# Lock.net
KiCad netlist of a schematic drawn in EAGLE
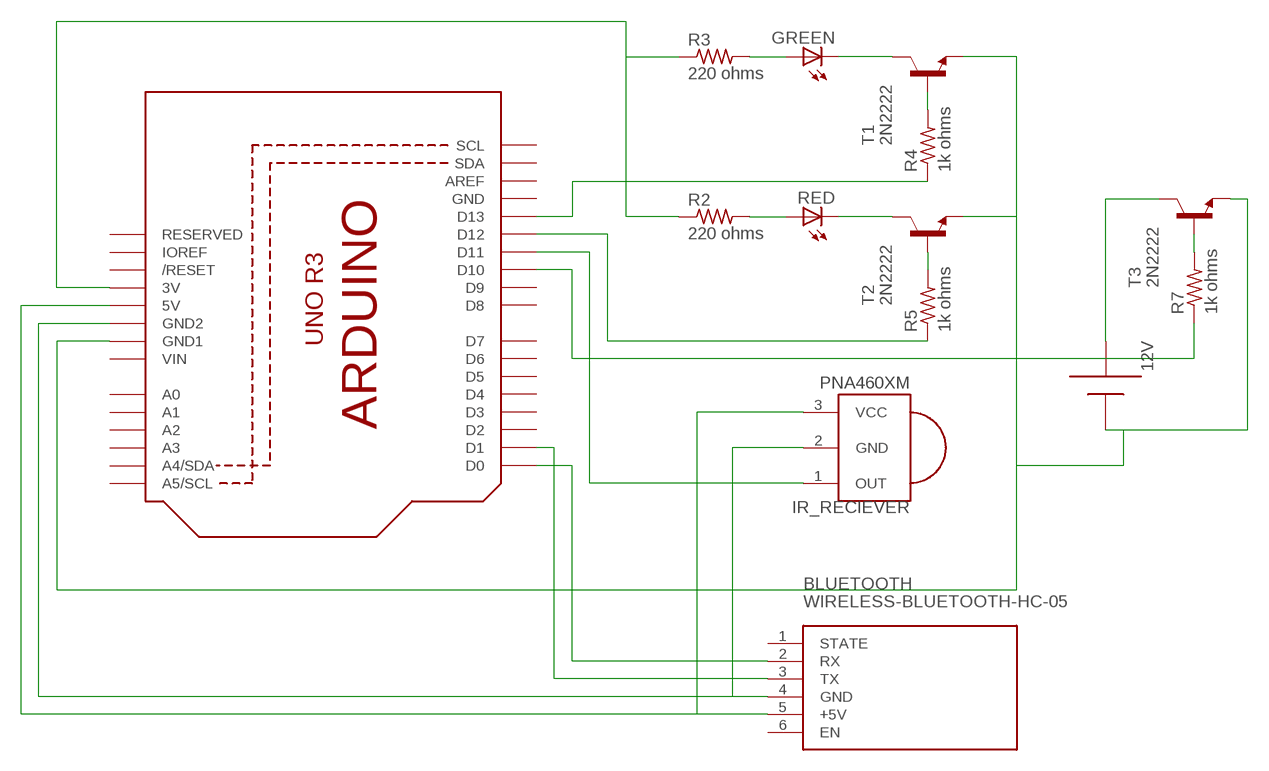
[diagram p0: schematic, sheet 1]

(export (version "E")
  (design (tool "Eeschema 10.0.6"))
  (components
    (comp (ref "12V")
      (value "AAA")
      (footprint "eagle-import:12BH412")
      (libsource (lib "eagle-import") (part "AAA"))
    )
    (comp (ref "BLUETOOTH")
      (value "WIRELESS-BLUETOOTH-HC-05")
      (footprint "eagle-import:WIRELESS-BLUETOOTH-HC-05")
      (libsource (lib "eagle-import") (part "WIRELESS-BLUETOOTH-HC-05"))
    )
    (comp (ref "GREEN")
      (value "LED3MM")
      (footprint "eagle-import:LED3MM")
      (libsource (lib "eagle-import") (part "LED3MM"))
    )
    (comp (ref "IR_RECIEVER")
      (value "PNA460XM")
      (footprint "eagle-import:PNA460XM")
      (libsource (lib "eagle-import") (part "PNA460XM"))
    )
    (comp (ref "R2")
      (value "220 ohms")
      (footprint "eagle-import:R1005")
      (libsource (lib "eagle-import") (part "R-US_R1005"))
    )
    (comp (ref "R3")
      (value "220 ohms")
      (footprint "eagle-import:R1005")
      (libsource (lib "eagle-import") (part "R-US_R1005"))
    )
    (comp (ref "R4")
      (value "1k ohms")
      (footprint "eagle-import:R1005")
      (libsource (lib "eagle-import") (part "R-US_R1005"))
    )
    (comp (ref "R5")
      (value "1k ohms")
      (footprint "eagle-import:R1005")
      (libsource (lib "eagle-import") (part "R-US_R1005"))
    )
    (comp (ref "R7")
      (value "1k ohms")
      (footprint "eagle-import:R1005")
      (libsource (lib "eagle-import") (part "R-US_R1005"))
    )
    (comp (ref "RED")
      (value "LED3MM")
      (footprint "eagle-import:LED3MM")
      (libsource (lib "eagle-import") (part "LED3MM"))
    )
    (comp (ref "T1")
      (value "2N2222")
      (footprint "eagle-import:TO92-EBC-OVAL")
      (libsource (lib "eagle-import") (part "2N2222"))
    )
    (comp (ref "T2")
      (value "2N2222")
      (footprint "eagle-import:TO92-EBC-OVAL")
      (libsource (lib "eagle-import") (part "2N2222"))
    )
    (comp (ref "T3")
      (value "2N2222")
      (footprint "eagle-import:TO92-EBC-OVAL")
      (libsource (lib "eagle-import") (part "2N2222"))
    )
    (comp (ref "U1")
      (value "ARDUINOR3-BPLACE")
      (footprint "eagle-import:ARDUINOR3-BPLACE")
      (libsource (lib "eagle-import") (part "ARDUINOR3-BPLACE"))
    )
  )
  (nets
    (net (code "1") (name "/GND") (class "Default")
      (node (ref "U1") (pin "GND") (pinfunction "GND_GND") (pintype "power_in"))
    )
    (net (code "2") (name "/VIN") (class "Default")
      (node (ref "U1") (pin "VIN") (pinfunction "VIN_VIN") (pintype "power_in"))
    )
    (net (code "3") (name "Net-(12V-Pad+)") (class "Default")
      (node (ref "12V") (pin "+") (pinfunction "+_+") (pintype "bidirectional"))
      (node (ref "T1") (pin "E") (pinfunction "E_E") (pintype "passive"))
      (node (ref "T2") (pin "E") (pinfunction "E_E") (pintype "passive"))
      (node (ref "T3") (pin "E") (pinfunction "E_E") (pintype "passive"))
      (node (ref "U1") (pin "GND1") (pinfunction "GND1_GND1") (pintype "power_in"))
    )
    (net (code "4") (name "Net-(12V-Pad-)") (class "Default")
      (node (ref "12V") (pin "-") (pinfunction "-_-") (pintype "bidirectional"))
      (node (ref "T3") (pin "C") (pinfunction "C_C") (pintype "passive"))
    )
    (net (code "5") (name "Net-(BLUETOOTH-+5V)") (class "Default")
      (node (ref "BLUETOOTH") (pin "5") (pinfunction "+5V_5") (pintype "power_in"))
      (node (ref "IR_RECIEVER") (pin "3") (pinfunction "VCC_3") (pintype "power_in"))
      (node (ref "U1") (pin "5V") (pinfunction "5V_5V") (pintype "power_in"))
    )
    (net (code "6") (name "Net-(BLUETOOTH-GND)") (class "Default")
      (node (ref "BLUETOOTH") (pin "4") (pinfunction "GND_4") (pintype "power_in"))
      (node (ref "IR_RECIEVER") (pin "2") (pinfunction "GND_2") (pintype "power_in"))
      (node (ref "U1") (pin "GND2") (pinfunction "GND2_GND2") (pintype "power_in"))
    )
    (net (code "7") (name "Net-(BLUETOOTH-RX)") (class "Default")
      (node (ref "BLUETOOTH") (pin "2") (pinfunction "RX_2") (pintype "bidirectional"))
      (node (ref "U1") (pin "D0") (pinfunction "D0_D0") (pintype "bidirectional"))
    )
    (net (code "8") (name "Net-(BLUETOOTH-TX)") (class "Default")
      (node (ref "BLUETOOTH") (pin "3") (pinfunction "TX_3") (pintype "bidirectional"))
      (node (ref "U1") (pin "D1") (pinfunction "D1_D1") (pintype "bidirectional"))
    )
    (net (code "9") (name "Net-(GREEN-C)") (class "Default")
      (node (ref "GREEN") (pin "K") (pinfunction "C_K") (pintype "passive"))
      (node (ref "T1") (pin "C") (pinfunction "C_C") (pintype "passive"))
    )
    (net (code "10") (name "Net-(GREEN-PadA)") (class "Default")
      (node (ref "GREEN") (pin "A") (pinfunction "A_A") (pintype "passive"))
      (node (ref "R3") (pin "2") (pinfunction "2_2") (pintype "passive"))
    )
    (net (code "11") (name "Net-(IR_RECIEVER-OUT)") (class "Default")
      (node (ref "IR_RECIEVER") (pin "1") (pinfunction "OUT_1") (pintype "output"))
      (node (ref "U1") (pin "D11") (pinfunction "D11_D11") (pintype "bidirectional"))
    )
    (net (code "12") (name "Net-(R2-Pad1)") (class "Default")
      (node (ref "R2") (pin "1") (pinfunction "1_1") (pintype "passive"))
      (node (ref "R3") (pin "1") (pinfunction "1_1") (pintype "passive"))
      (node (ref "U1") (pin "3V") (pinfunction "3V_3V") (pintype "power_in"))
    )
    (net (code "13") (name "Net-(R2-Pad2)") (class "Default")
      (node (ref "R2") (pin "2") (pinfunction "2_2") (pintype "passive"))
      (node (ref "RED") (pin "A") (pinfunction "A_A") (pintype "passive"))
    )
    (net (code "14") (name "Net-(R4-Pad1)") (class "Default")
      (node (ref "R4") (pin "1") (pinfunction "1_1") (pintype "passive"))
      (node (ref "U1") (pin "D13") (pinfunction "D13_D13") (pintype "bidirectional"))
    )
    (net (code "15") (name "Net-(R4-Pad2)") (class "Default")
      (node (ref "R4") (pin "2") (pinfunction "2_2") (pintype "passive"))
      (node (ref "T1") (pin "B") (pinfunction "B_B") (pintype "passive"))
    )
    (net (code "16") (name "Net-(R5-Pad1)") (class "Default")
      (node (ref "R5") (pin "1") (pinfunction "1_1") (pintype "passive"))
      (node (ref "U1") (pin "D12") (pinfunction "D12_D12") (pintype "bidirectional"))
    )
    (net (code "17") (name "Net-(R5-Pad2)") (class "Default")
      (node (ref "R5") (pin "2") (pinfunction "2_2") (pintype "passive"))
      (node (ref "T2") (pin "B") (pinfunction "B_B") (pintype "passive"))
    )
    (net (code "18") (name "Net-(R7-Pad1)") (class "Default")
      (node (ref "R7") (pin "1") (pinfunction "1_1") (pintype "passive"))
      (node (ref "U1") (pin "D10") (pinfunction "D10_D10") (pintype "bidirectional"))
    )
    (net (code "19") (name "Net-(R7-Pad2)") (class "Default")
      (node (ref "R7") (pin "2") (pinfunction "2_2") (pintype "passive"))
      (node (ref "T3") (pin "B") (pinfunction "B_B") (pintype "passive"))
    )
    (net (code "20") (name "Net-(RED-C)") (class "Default")
      (node (ref "RED") (pin "K") (pinfunction "C_K") (pintype "passive"))
      (node (ref "T2") (pin "C") (pinfunction "C_C") (pintype "passive"))
    )
    (net (code "21") (name "unconnected-(BLUETOOTH-EN-Pad6)") (class "Default")
      (node (ref "BLUETOOTH") (pin "6") (pinfunction "EN_6") (pintype "bidirectional"))
    )
    (net (code "22") (name "unconnected-(BLUETOOTH-STATE-Pad1)") (class "Default")
      (node (ref "BLUETOOTH") (pin "1") (pinfunction "STATE_1") (pintype "bidirectional"))
    )
    (net (code "23") (name "unconnected-(U1-A4{slash}SDA-PadA4)") (class "Default")
      (node (ref "U1") (pin "A4") (pinfunction "A4/SDA_A4") (pintype "bidirectional"))
    )
    (net (code "24") (name "unconnected-(U1-A5{slash}SCL-PadA5)") (class "Default")
      (node (ref "U1") (pin "A5") (pinfunction "A5/SCL_A5") (pintype "bidirectional"))
    )
    (net (code "25") (name "unconnected-(U1-PadA0)") (class "Default")
      (node (ref "U1") (pin "A0") (pinfunction "A0_A0") (pintype "bidirectional"))
    )
    (net (code "26") (name "unconnected-(U1-PadA1)") (class "Default")
      (node (ref "U1") (pin "A1") (pinfunction "A1_A1") (pintype "bidirectional"))
    )
    (net (code "27") (name "unconnected-(U1-PadA2)") (class "Default")
      (node (ref "U1") (pin "A2") (pinfunction "A2_A2") (pintype "bidirectional"))
    )
    (net (code "28") (name "unconnected-(U1-PadA3)") (class "Default")
      (node (ref "U1") (pin "A3") (pinfunction "A3_A3") (pintype "bidirectional"))
    )
    (net (code "29") (name "unconnected-(U1-PadAREF)") (class "Default")
      (node (ref "U1") (pin "AREF") (pinfunction "AREF_AREF") (pintype "bidirectional"))
    )
    (net (code "30") (name "unconnected-(U1-PadD2)") (class "Default")
      (node (ref "U1") (pin "D2") (pinfunction "D2_D2") (pintype "bidirectional"))
    )
    (net (code "31") (name "unconnected-(U1-PadD3)") (class "Default")
      (node (ref "U1") (pin "D3") (pinfunction "D3_D3") (pintype "bidirectional"))
    )
    (net (code "32") (name "unconnected-(U1-PadD4)") (class "Default")
      (node (ref "U1") (pin "D4") (pinfunction "D4_D4") (pintype "bidirectional"))
    )
    (net (code "33") (name "unconnected-(U1-PadD5)") (class "Default")
      (node (ref "U1") (pin "D5") (pinfunction "D5_D5") (pintype "bidirectional"))
    )
    (net (code "34") (name "unconnected-(U1-PadD6)") (class "Default")
      (node (ref "U1") (pin "D6") (pinfunction "D6_D6") (pintype "bidirectional"))
    )
    (net (code "35") (name "unconnected-(U1-PadD7)") (class "Default")
      (node (ref "U1") (pin "D7") (pinfunction "D7_D7") (pintype "bidirectional"))
    )
    (net (code "36") (name "unconnected-(U1-PadD8)") (class "Default")
      (node (ref "U1") (pin "D8") (pinfunction "D8_D8") (pintype "bidirectional"))
    )
    (net (code "37") (name "unconnected-(U1-PadD9)") (class "Default")
      (node (ref "U1") (pin "D9") (pinfunction "D9_D9") (pintype "bidirectional"))
    )
    (net (code "38") (name "unconnected-(U1-PadIOREF)") (class "Default")
      (node (ref "U1") (pin "IOREF") (pinfunction "IOREF_IOREF") (pintype "output"))
    )
    (net (code "39") (name "unconnected-(U1-PadRESERVED)") (class "Default")
      (node (ref "U1") (pin "RESERVED") (pinfunction "RESERVED_RESERVED") (pintype "no_connect"))
    )
    (net (code "40") (name "unconnected-(U1-PadSCL)") (class "Default")
      (node (ref "U1") (pin "SCL") (pinfunction "SCL_SCL") (pintype "bidirectional"))
    )
    (net (code "41") (name "unconnected-(U1-PadSDA)") (class "Default")
      (node (ref "U1") (pin "SDA") (pinfunction "SDA_SDA") (pintype "bidirectional"))
    )
    (net (code "42") (name "unconnected-(U1-{slash}RESET-PadRESET)") (class "Default")
      (node (ref "U1") (pin "RESET") (pinfunction "/RESET_RESET") (pintype "bidirectional"))
    )
  )
)
